# M113.net
KiCad netlist of a schematic drawn in EAGLE
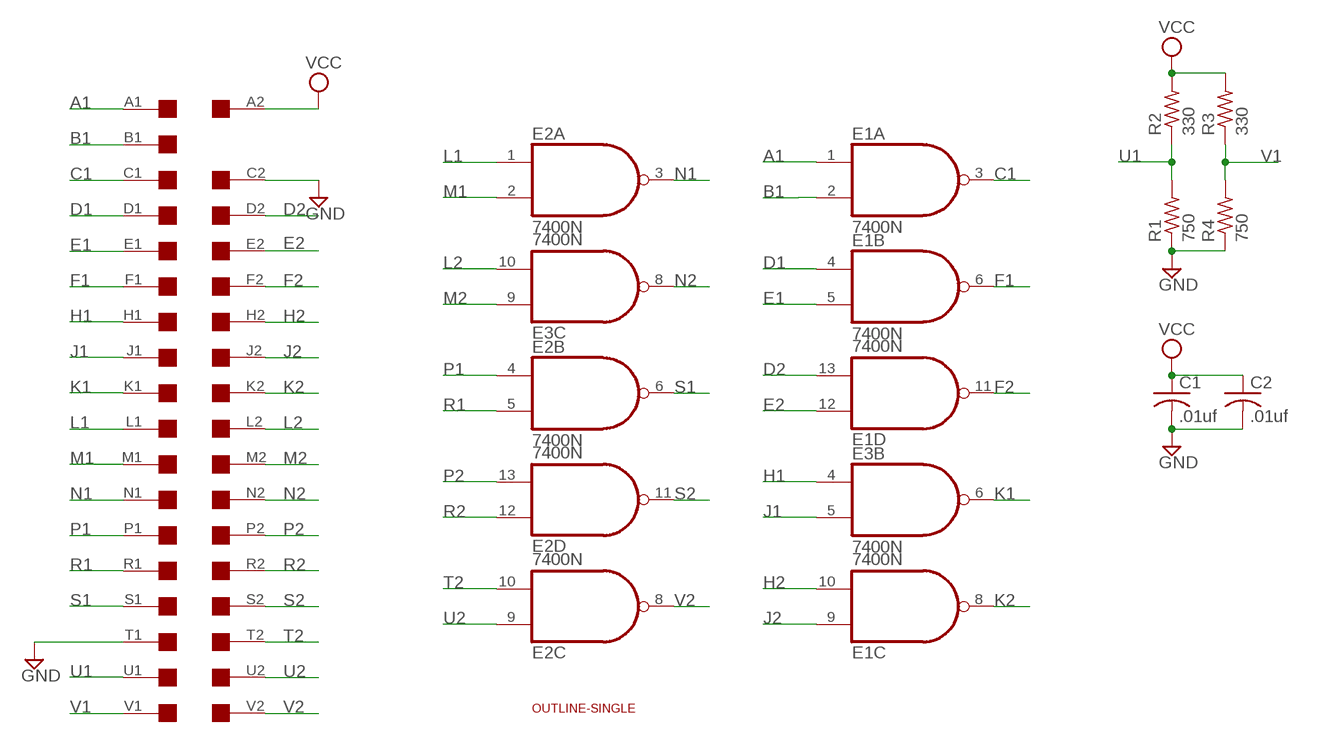
[diagram p0: schematic, sheet 1]

(export (version "E")
  (design (tool "Eeschema 10.0.6"))
  (components
    (comp (ref "C1")
      (value ".01uf")
      (footprint "eagle-import:C050-025X075")
      (libsource (lib "eagle-import") (part "C-US050-025X075"))
    )
    (comp (ref "C2")
      (value ".01uf")
      (footprint "eagle-import:C050-025X075")
      (libsource (lib "eagle-import") (part "C-US050-025X075"))
    )
    (comp (ref "E1")
      (value "7400N")
      (footprint "eagle-import:DIL14")
      (libsource (lib "eagle-import") (part "7400N"))
    )
    (comp (ref "E2")
      (value "7400N")
      (footprint "eagle-import:DIL14")
      (libsource (lib "eagle-import") (part "7400N"))
    )
    (comp (ref "E3")
      (value "7400N")
      (footprint "eagle-import:DIL14")
      (libsource (lib "eagle-import") (part "7400N"))
    )
    (comp (ref "R1")
      (value "750")
      (footprint "eagle-import:0207_10")
      (libsource (lib "eagle-import") (part "R-US_0207/10"))
    )
    (comp (ref "R2")
      (value "330")
      (footprint "eagle-import:0207_10")
      (libsource (lib "eagle-import") (part "R-US_0207/10"))
    )
    (comp (ref "R3")
      (value "330")
      (footprint "eagle-import:0207_10")
      (libsource (lib "eagle-import") (part "R-US_0207/10"))
    )
    (comp (ref "R4")
      (value "750")
      (footprint "eagle-import:0207_10")
      (libsource (lib "eagle-import") (part "R-US_0207/10"))
    )
    (comp (ref "U$1")
      (value "SINGLE")
      (footprint "eagle-import:EDGE-CON2")
      (libsource (lib "eagle-import") (part "SINGLE"))
    )
    (comp (ref "U$2")
      (value "OUTLINE-SINGLE")
      (footprint "eagle-import:SINGLE")
      (libsource (lib "eagle-import") (part "OUTLINE-SINGLE"))
    )
  )
  (nets
    (net (code "1") (name "/A1") (class "Default")
      (node (ref "E1") (pin "1") (pinfunction "I0_1") (pintype "input"))
      (node (ref "U$1") (pin "A1") (pinfunction "1_A1") (pintype "bidirectional"))
    )
    (net (code "2") (name "/B1") (class "Default")
      (node (ref "E1") (pin "2") (pinfunction "I1_2") (pintype "input"))
      (node (ref "U$1") (pin "B1") (pinfunction "1_B1") (pintype "bidirectional"))
    )
    (net (code "3") (name "/C1") (class "Default")
      (node (ref "E1") (pin "3") (pinfunction "O_3") (pintype "output"))
      (node (ref "U$1") (pin "C1") (pinfunction "1_C1") (pintype "bidirectional"))
    )
    (net (code "4") (name "/D1") (class "Default")
      (node (ref "E1") (pin "4") (pinfunction "I0_4") (pintype "input"))
      (node (ref "U$1") (pin "D1") (pinfunction "1_D1") (pintype "bidirectional"))
    )
    (net (code "5") (name "/D2") (class "Default")
      (node (ref "E1") (pin "13") (pinfunction "I1_13") (pintype "input"))
      (node (ref "U$1") (pin "D2") (pinfunction "1_D2") (pintype "bidirectional"))
    )
    (net (code "6") (name "/E1") (class "Default")
      (node (ref "E1") (pin "5") (pinfunction "I1_5") (pintype "input"))
      (node (ref "U$1") (pin "E1") (pinfunction "1_E1") (pintype "bidirectional"))
    )
    (net (code "7") (name "/E2") (class "Default")
      (node (ref "E1") (pin "12") (pinfunction "I0_12") (pintype "input"))
      (node (ref "U$1") (pin "E2") (pinfunction "1_E2") (pintype "bidirectional"))
    )
    (net (code "8") (name "/F1") (class "Default")
      (node (ref "E1") (pin "6") (pinfunction "O_6") (pintype "output"))
      (node (ref "U$1") (pin "F1") (pinfunction "1_F1") (pintype "bidirectional"))
    )
    (net (code "9") (name "/F2") (class "Default")
      (node (ref "E1") (pin "11") (pinfunction "O_11") (pintype "output"))
      (node (ref "U$1") (pin "F2") (pinfunction "1_F2") (pintype "bidirectional"))
    )
    (net (code "10") (name "/H1") (class "Default")
      (node (ref "E3") (pin "4") (pinfunction "I0_4") (pintype "input"))
      (node (ref "U$1") (pin "H1") (pinfunction "1_H1") (pintype "bidirectional"))
    )
    (net (code "11") (name "/H2") (class "Default")
      (node (ref "E1") (pin "10") (pinfunction "I1_10") (pintype "input"))
      (node (ref "U$1") (pin "H2") (pinfunction "1_H2") (pintype "bidirectional"))
    )
    (net (code "12") (name "/J1") (class "Default")
      (node (ref "E3") (pin "5") (pinfunction "I1_5") (pintype "input"))
      (node (ref "U$1") (pin "J1") (pinfunction "1_J1") (pintype "bidirectional"))
    )
    (net (code "13") (name "/J2") (class "Default")
      (node (ref "E1") (pin "9") (pinfunction "I0_9") (pintype "input"))
      (node (ref "U$1") (pin "J2") (pinfunction "1_J2") (pintype "bidirectional"))
    )
    (net (code "14") (name "/K1") (class "Default")
      (node (ref "E3") (pin "6") (pinfunction "O_6") (pintype "output"))
      (node (ref "U$1") (pin "K1") (pinfunction "1_K1") (pintype "bidirectional"))
    )
    (net (code "15") (name "/K2") (class "Default")
      (node (ref "E1") (pin "8") (pinfunction "O_8") (pintype "output"))
      (node (ref "U$1") (pin "K2") (pinfunction "1_K2") (pintype "bidirectional"))
    )
    (net (code "16") (name "/L1") (class "Default")
      (node (ref "E2") (pin "1") (pinfunction "I0_1") (pintype "input"))
      (node (ref "U$1") (pin "L1") (pinfunction "1_L1") (pintype "bidirectional"))
    )
    (net (code "17") (name "/L2") (class "Default")
      (node (ref "E3") (pin "10") (pinfunction "I1_10") (pintype "input"))
      (node (ref "U$1") (pin "L2") (pinfunction "1_L2") (pintype "bidirectional"))
    )
    (net (code "18") (name "/M1") (class "Default")
      (node (ref "E2") (pin "2") (pinfunction "I1_2") (pintype "input"))
      (node (ref "U$1") (pin "M1") (pinfunction "1_M1") (pintype "bidirectional"))
    )
    (net (code "19") (name "/M2") (class "Default")
      (node (ref "E3") (pin "9") (pinfunction "I0_9") (pintype "input"))
      (node (ref "U$1") (pin "M2") (pinfunction "1_M2") (pintype "bidirectional"))
    )
    (net (code "20") (name "/N1") (class "Default")
      (node (ref "E2") (pin "3") (pinfunction "O_3") (pintype "output"))
      (node (ref "U$1") (pin "N1") (pinfunction "1_N1") (pintype "bidirectional"))
    )
    (net (code "21") (name "/N2") (class "Default")
      (node (ref "E3") (pin "8") (pinfunction "O_8") (pintype "output"))
      (node (ref "U$1") (pin "N2") (pinfunction "1_N2") (pintype "bidirectional"))
    )
    (net (code "22") (name "/P1") (class "Default")
      (node (ref "E2") (pin "4") (pinfunction "I0_4") (pintype "input"))
      (node (ref "U$1") (pin "P1") (pinfunction "1_P1") (pintype "bidirectional"))
    )
    (net (code "23") (name "/P2") (class "Default")
      (node (ref "E2") (pin "13") (pinfunction "I1_13") (pintype "input"))
      (node (ref "U$1") (pin "P2") (pinfunction "1_P2") (pintype "bidirectional"))
    )
    (net (code "24") (name "/R1") (class "Default")
      (node (ref "E2") (pin "5") (pinfunction "I1_5") (pintype "input"))
      (node (ref "U$1") (pin "R1") (pinfunction "1_R1") (pintype "bidirectional"))
    )
    (net (code "25") (name "/R2") (class "Default")
      (node (ref "E2") (pin "12") (pinfunction "I0_12") (pintype "input"))
      (node (ref "U$1") (pin "R2") (pinfunction "1_R2") (pintype "bidirectional"))
    )
    (net (code "26") (name "/S1") (class "Default")
      (node (ref "E2") (pin "6") (pinfunction "O_6") (pintype "output"))
      (node (ref "U$1") (pin "S1") (pinfunction "1_S1") (pintype "bidirectional"))
    )
    (net (code "27") (name "/S2") (class "Default")
      (node (ref "E2") (pin "11") (pinfunction "O_11") (pintype "output"))
      (node (ref "U$1") (pin "S2") (pinfunction "1_S2") (pintype "bidirectional"))
    )
    (net (code "28") (name "/T2") (class "Default")
      (node (ref "E2") (pin "10") (pinfunction "I1_10") (pintype "input"))
      (node (ref "U$1") (pin "T2") (pinfunction "1_T2") (pintype "bidirectional"))
    )
    (net (code "29") (name "/U1") (class "Default")
      (node (ref "R1") (pin "2") (pinfunction "2_2") (pintype "passive"))
      (node (ref "R2") (pin "1") (pinfunction "1_1") (pintype "passive"))
      (node (ref "U$1") (pin "U1") (pinfunction "1_U1") (pintype "bidirectional"))
    )
    (net (code "30") (name "/U2") (class "Default")
      (node (ref "E2") (pin "9") (pinfunction "I0_9") (pintype "input"))
      (node (ref "U$1") (pin "U2") (pinfunction "1_U2") (pintype "bidirectional"))
    )
    (net (code "31") (name "/V1") (class "Default")
      (node (ref "R3") (pin "1") (pinfunction "1_1") (pintype "passive"))
      (node (ref "R4") (pin "2") (pinfunction "2_2") (pintype "passive"))
      (node (ref "U$1") (pin "V1") (pinfunction "1_V1") (pintype "bidirectional"))
    )
    (net (code "32") (name "/V2") (class "Default")
      (node (ref "E2") (pin "8") (pinfunction "O_8") (pintype "output"))
      (node (ref "U$1") (pin "V2") (pinfunction "1_V2") (pintype "bidirectional"))
    )
    (net (code "33") (name "GND") (class "Default")
      (node (ref "C1") (pin "2") (pinfunction "2_2") (pintype "passive"))
      (node (ref "C2") (pin "2") (pinfunction "2_2") (pintype "passive"))
      (node (ref "R1") (pin "1") (pinfunction "1_1") (pintype "passive"))
      (node (ref "R4") (pin "1") (pinfunction "1_1") (pintype "passive"))
      (node (ref "U$1") (pin "C2") (pinfunction "1_C2") (pintype "bidirectional"))
      (node (ref "U$1") (pin "T1") (pinfunction "1_T1") (pintype "bidirectional"))
    )
    (net (code "34") (name "VCC") (class "Default")
      (node (ref "C1") (pin "1") (pinfunction "1_1") (pintype "passive"))
      (node (ref "C2") (pin "1") (pinfunction "1_1") (pintype "passive"))
      (node (ref "R2") (pin "2") (pinfunction "2_2") (pintype "passive"))
      (node (ref "R3") (pin "2") (pinfunction "2_2") (pintype "passive"))
      (node (ref "U$1") (pin "A2") (pinfunction "1_A2") (pintype "bidirectional"))
    )
  )
)
